# Lab_8_-_Schematic.net
KiCad netlist of a schematic drawn in EAGLE
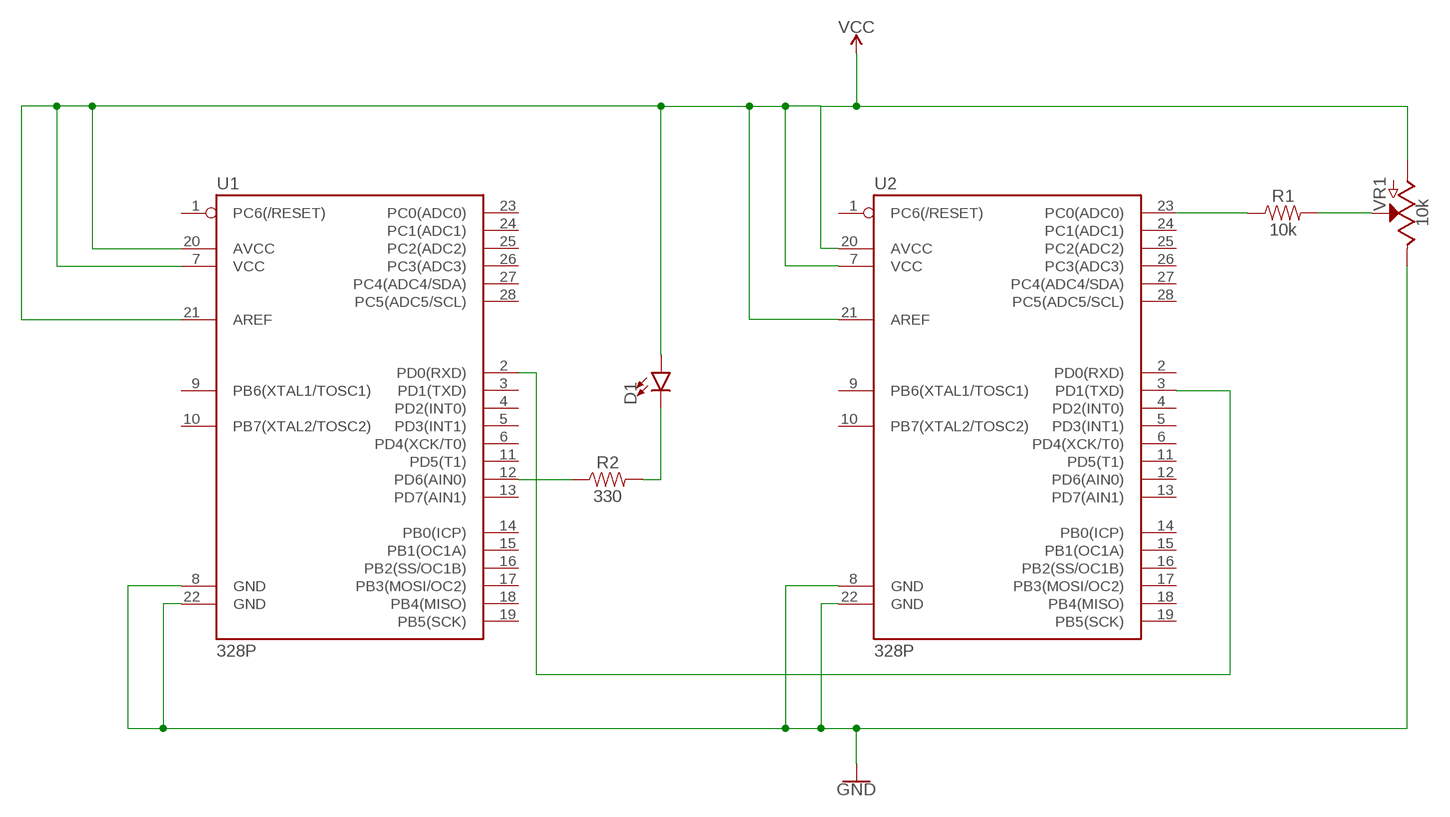
[diagram p0: schematic, sheet 1]

(export (version "E")
  (design (tool "Eeschema 10.0.6"))
  (components
    (comp (ref "D1")
      (value "LED3MM")
      (footprint "eagle-import:LED_3MM")
      (libsource (lib "eagle-import") (part "LED3MM"))
    )
    (comp (ref "R1")
      (value "10k")
      (footprint "eagle-import:AXIAL-0.3")
      (libsource (lib "eagle-import") (part "10KOHM-HORIZ-1/4W-5%"))
    )
    (comp (ref "R2")
      (value "330")
      (footprint "eagle-import:AXIAL-0.3")
      (libsource (lib "eagle-import") (part "330OHM-HORIZ-1/10W-5%"))
    )
    (comp (ref "U1")
      (value "328P")
      (footprint "eagle-import:DIP28")
      (libsource (lib "eagle-import") (part "ATMEGA328P_PDIP"))
    )
    (comp (ref "U2")
      (value "328P")
      (footprint "eagle-import:DIP28")
      (libsource (lib "eagle-import") (part "ATMEGA328P_PDIP"))
    )
    (comp (ref "VR1")
      (value "10k")
      (footprint "eagle-import:POT-PTH-ALPS-KIT")
      (libsource (lib "eagle-import") (part "POTENTIOMETER-PTH-9MM-1/20W-20%-KIT"))
    )
  )
  (nets
    (net (code "1") (name "GND") (class "Default")
      (node (ref "U1") (pin "22") (pinfunction "GND_22") (pintype "bidirectional"))
      (node (ref "U1") (pin "8") (pinfunction "GND_8") (pintype "bidirectional"))
      (node (ref "U2") (pin "22") (pinfunction "GND_22") (pintype "bidirectional"))
      (node (ref "U2") (pin "8") (pinfunction "GND_8") (pintype "bidirectional"))
      (node (ref "VR1") (pin "P$1") (pinfunction "E_P$1") (pintype "passive"))
    )
    (net (code "2") (name "Net-(D1-C)") (class "Default")
      (node (ref "D1") (pin "K") (pinfunction "C_K") (pintype "passive"))
      (node (ref "R2") (pin "P$2") (pinfunction "2_P$2") (pintype "passive"))
    )
    (net (code "3") (name "Net-(R1-1)") (class "Default")
      (node (ref "R1") (pin "P$1") (pinfunction "1_P$1") (pintype "passive"))
      (node (ref "U2") (pin "23") (pinfunction "PC0(ADC0)_23") (pintype "bidirectional"))
    )
    (net (code "4") (name "Net-(R1-2)") (class "Default")
      (node (ref "R1") (pin "P$2") (pinfunction "2_P$2") (pintype "passive"))
      (node (ref "VR1") (pin "P$2") (pinfunction "S_P$2") (pintype "passive"))
    )
    (net (code "5") (name "Net-(R2-1)") (class "Default")
      (node (ref "R2") (pin "P$1") (pinfunction "1_P$1") (pintype "passive"))
      (node (ref "U1") (pin "12") (pinfunction "PD6(AIN0)_12") (pintype "bidirectional"))
    )
    (net (code "6") (name "Net-(U1-PD0(RXD))") (class "Default")
      (node (ref "U1") (pin "2") (pinfunction "PD0(RXD)_2") (pintype "bidirectional"))
      (node (ref "U2") (pin "3") (pinfunction "PD1(TXD)_3") (pintype "bidirectional"))
    )
    (net (code "7") (name "VCC") (class "Default")
      (node (ref "D1") (pin "A") (pinfunction "A_A") (pintype "passive"))
      (node (ref "U1") (pin "20") (pinfunction "AVCC_20") (pintype "bidirectional"))
      (node (ref "U1") (pin "21") (pinfunction "AREF_21") (pintype "bidirectional"))
      (node (ref "U1") (pin "7") (pinfunction "VCC_7") (pintype "bidirectional"))
      (node (ref "U2") (pin "20") (pinfunction "AVCC_20") (pintype "bidirectional"))
      (node (ref "U2") (pin "21") (pinfunction "AREF_21") (pintype "bidirectional"))
      (node (ref "U2") (pin "7") (pinfunction "VCC_7") (pintype "bidirectional"))
      (node (ref "VR1") (pin "P$3") (pinfunction "A_P$3") (pintype "passive"))
    )
    (net (code "8") (name "unconnected-(U1-PB0(ICP)-Pad14)") (class "Default")
      (node (ref "U1") (pin "14") (pinfunction "PB0(ICP)_14") (pintype "bidirectional"))
    )
    (net (code "9") (name "unconnected-(U1-PB1(OC1A)-Pad15)") (class "Default")
      (node (ref "U1") (pin "15") (pinfunction "PB1(OC1A)_15") (pintype "bidirectional"))
    )
    (net (code "10") (name "unconnected-(U1-PB2(SS{slash}OC1B)-Pad16)") (class "Default")
      (node (ref "U1") (pin "16") (pinfunction "PB2(SS/OC1B)_16") (pintype "bidirectional"))
    )
    (net (code "11") (name "unconnected-(U1-PB3(MOSI{slash}OC2)-Pad17)") (class "Default")
      (node (ref "U1") (pin "17") (pinfunction "PB3(MOSI/OC2)_17") (pintype "bidirectional"))
    )
    (net (code "12") (name "unconnected-(U1-PB4(MISO)-Pad18)") (class "Default")
      (node (ref "U1") (pin "18") (pinfunction "PB4(MISO)_18") (pintype "bidirectional"))
    )
    (net (code "13") (name "unconnected-(U1-PB5(SCK)-Pad19)") (class "Default")
      (node (ref "U1") (pin "19") (pinfunction "PB5(SCK)_19") (pintype "bidirectional"))
    )
    (net (code "14") (name "unconnected-(U1-PB6(XTAL1{slash}TOSC1)-Pad9)") (class "Default")
      (node (ref "U1") (pin "9") (pinfunction "PB6(XTAL1/TOSC1)_9") (pintype "bidirectional"))
    )
    (net (code "15") (name "unconnected-(U1-PB7(XTAL2{slash}TOSC2)-Pad10)") (class "Default")
      (node (ref "U1") (pin "10") (pinfunction "PB7(XTAL2/TOSC2)_10") (pintype "bidirectional"))
    )
    (net (code "16") (name "unconnected-(U1-PC0(ADC0)-Pad23)") (class "Default")
      (node (ref "U1") (pin "23") (pinfunction "PC0(ADC0)_23") (pintype "bidirectional"))
    )
    (net (code "17") (name "unconnected-(U1-PC1(ADC1)-Pad24)") (class "Default")
      (node (ref "U1") (pin "24") (pinfunction "PC1(ADC1)_24") (pintype "bidirectional"))
    )
    (net (code "18") (name "unconnected-(U1-PC2(ADC2)-Pad25)") (class "Default")
      (node (ref "U1") (pin "25") (pinfunction "PC2(ADC2)_25") (pintype "bidirectional"))
    )
    (net (code "19") (name "unconnected-(U1-PC3(ADC3)-Pad26)") (class "Default")
      (node (ref "U1") (pin "26") (pinfunction "PC3(ADC3)_26") (pintype "bidirectional"))
    )
    (net (code "20") (name "unconnected-(U1-PC4(ADC4{slash}SDA)-Pad27)") (class "Default")
      (node (ref "U1") (pin "27") (pinfunction "PC4(ADC4/SDA)_27") (pintype "bidirectional"))
    )
    (net (code "21") (name "unconnected-(U1-PC5(ADC5{slash}SCL)-Pad28)") (class "Default")
      (node (ref "U1") (pin "28") (pinfunction "PC5(ADC5/SCL)_28") (pintype "bidirectional"))
    )
    (net (code "22") (name "unconnected-(U1-PC6({slash}RESET)-Pad1)") (class "Default")
      (node (ref "U1") (pin "1") (pinfunction "PC6(/RESET)_1") (pintype "bidirectional"))
    )
    (net (code "23") (name "unconnected-(U1-PD1(TXD)-Pad3)") (class "Default")
      (node (ref "U1") (pin "3") (pinfunction "PD1(TXD)_3") (pintype "bidirectional"))
    )
    (net (code "24") (name "unconnected-(U1-PD2(INT0)-Pad4)") (class "Default")
      (node (ref "U1") (pin "4") (pinfunction "PD2(INT0)_4") (pintype "bidirectional"))
    )
    (net (code "25") (name "unconnected-(U1-PD3(INT1)-Pad5)") (class "Default")
      (node (ref "U1") (pin "5") (pinfunction "PD3(INT1)_5") (pintype "bidirectional"))
    )
    (net (code "26") (name "unconnected-(U1-PD4(XCK{slash}T0)-Pad6)") (class "Default")
      (node (ref "U1") (pin "6") (pinfunction "PD4(XCK/T0)_6") (pintype "bidirectional"))
    )
    (net (code "27") (name "unconnected-(U1-PD5(T1)-Pad11)") (class "Default")
      (node (ref "U1") (pin "11") (pinfunction "PD5(T1)_11") (pintype "bidirectional"))
    )
    (net (code "28") (name "unconnected-(U1-PD7(AIN1)-Pad13)") (class "Default")
      (node (ref "U1") (pin "13") (pinfunction "PD7(AIN1)_13") (pintype "bidirectional"))
    )
    (net (code "29") (name "unconnected-(U2-PB0(ICP)-Pad14)") (class "Default")
      (node (ref "U2") (pin "14") (pinfunction "PB0(ICP)_14") (pintype "bidirectional"))
    )
    (net (code "30") (name "unconnected-(U2-PB1(OC1A)-Pad15)") (class "Default")
      (node (ref "U2") (pin "15") (pinfunction "PB1(OC1A)_15") (pintype "bidirectional"))
    )
    (net (code "31") (name "unconnected-(U2-PB2(SS{slash}OC1B)-Pad16)") (class "Default")
      (node (ref "U2") (pin "16") (pinfunction "PB2(SS/OC1B)_16") (pintype "bidirectional"))
    )
    (net (code "32") (name "unconnected-(U2-PB3(MOSI{slash}OC2)-Pad17)") (class "Default")
      (node (ref "U2") (pin "17") (pinfunction "PB3(MOSI/OC2)_17") (pintype "bidirectional"))
    )
    (net (code "33") (name "unconnected-(U2-PB4(MISO)-Pad18)") (class "Default")
      (node (ref "U2") (pin "18") (pinfunction "PB4(MISO)_18") (pintype "bidirectional"))
    )
    (net (code "34") (name "unconnected-(U2-PB5(SCK)-Pad19)") (class "Default")
      (node (ref "U2") (pin "19") (pinfunction "PB5(SCK)_19") (pintype "bidirectional"))
    )
    (net (code "35") (name "unconnected-(U2-PB6(XTAL1{slash}TOSC1)-Pad9)") (class "Default")
      (node (ref "U2") (pin "9") (pinfunction "PB6(XTAL1/TOSC1)_9") (pintype "bidirectional"))
    )
    (net (code "36") (name "unconnected-(U2-PB7(XTAL2{slash}TOSC2)-Pad10)") (class "Default")
      (node (ref "U2") (pin "10") (pinfunction "PB7(XTAL2/TOSC2)_10") (pintype "bidirectional"))
    )
    (net (code "37") (name "unconnected-(U2-PC1(ADC1)-Pad24)") (class "Default")
      (node (ref "U2") (pin "24") (pinfunction "PC1(ADC1)_24") (pintype "bidirectional"))
    )
    (net (code "38") (name "unconnected-(U2-PC2(ADC2)-Pad25)") (class "Default")
      (node (ref "U2") (pin "25") (pinfunction "PC2(ADC2)_25") (pintype "bidirectional"))
    )
    (net (code "39") (name "unconnected-(U2-PC3(ADC3)-Pad26)") (class "Default")
      (node (ref "U2") (pin "26") (pinfunction "PC3(ADC3)_26") (pintype "bidirectional"))
    )
    (net (code "40") (name "unconnected-(U2-PC4(ADC4{slash}SDA)-Pad27)") (class "Default")
      (node (ref "U2") (pin "27") (pinfunction "PC4(ADC4/SDA)_27") (pintype "bidirectional"))
    )
    (net (code "41") (name "unconnected-(U2-PC5(ADC5{slash}SCL)-Pad28)") (class "Default")
      (node (ref "U2") (pin "28") (pinfunction "PC5(ADC5/SCL)_28") (pintype "bidirectional"))
    )
    (net (code "42") (name "unconnected-(U2-PC6({slash}RESET)-Pad1)") (class "Default")
      (node (ref "U2") (pin "1") (pinfunction "PC6(/RESET)_1") (pintype "bidirectional"))
    )
    (net (code "43") (name "unconnected-(U2-PD0(RXD)-Pad2)") (class "Default")
      (node (ref "U2") (pin "2") (pinfunction "PD0(RXD)_2") (pintype "bidirectional"))
    )
    (net (code "44") (name "unconnected-(U2-PD2(INT0)-Pad4)") (class "Default")
      (node (ref "U2") (pin "4") (pinfunction "PD2(INT0)_4") (pintype "bidirectional"))
    )
    (net (code "45") (name "unconnected-(U2-PD3(INT1)-Pad5)") (class "Default")
      (node (ref "U2") (pin "5") (pinfunction "PD3(INT1)_5") (pintype "bidirectional"))
    )
    (net (code "46") (name "unconnected-(U2-PD4(XCK{slash}T0)-Pad6)") (class "Default")
      (node (ref "U2") (pin "6") (pinfunction "PD4(XCK/T0)_6") (pintype "bidirectional"))
    )
    (net (code "47") (name "unconnected-(U2-PD5(T1)-Pad11)") (class "Default")
      (node (ref "U2") (pin "11") (pinfunction "PD5(T1)_11") (pintype "bidirectional"))
    )
    (net (code "48") (name "unconnected-(U2-PD6(AIN0)-Pad12)") (class "Default")
      (node (ref "U2") (pin "12") (pinfunction "PD6(AIN0)_12") (pintype "bidirectional"))
    )
    (net (code "49") (name "unconnected-(U2-PD7(AIN1)-Pad13)") (class "Default")
      (node (ref "U2") (pin "13") (pinfunction "PD7(AIN1)_13") (pintype "bidirectional"))
    )
  )
)
